# Regulators_block.net
KiCad netlist of a schematic drawn in Altium Designer
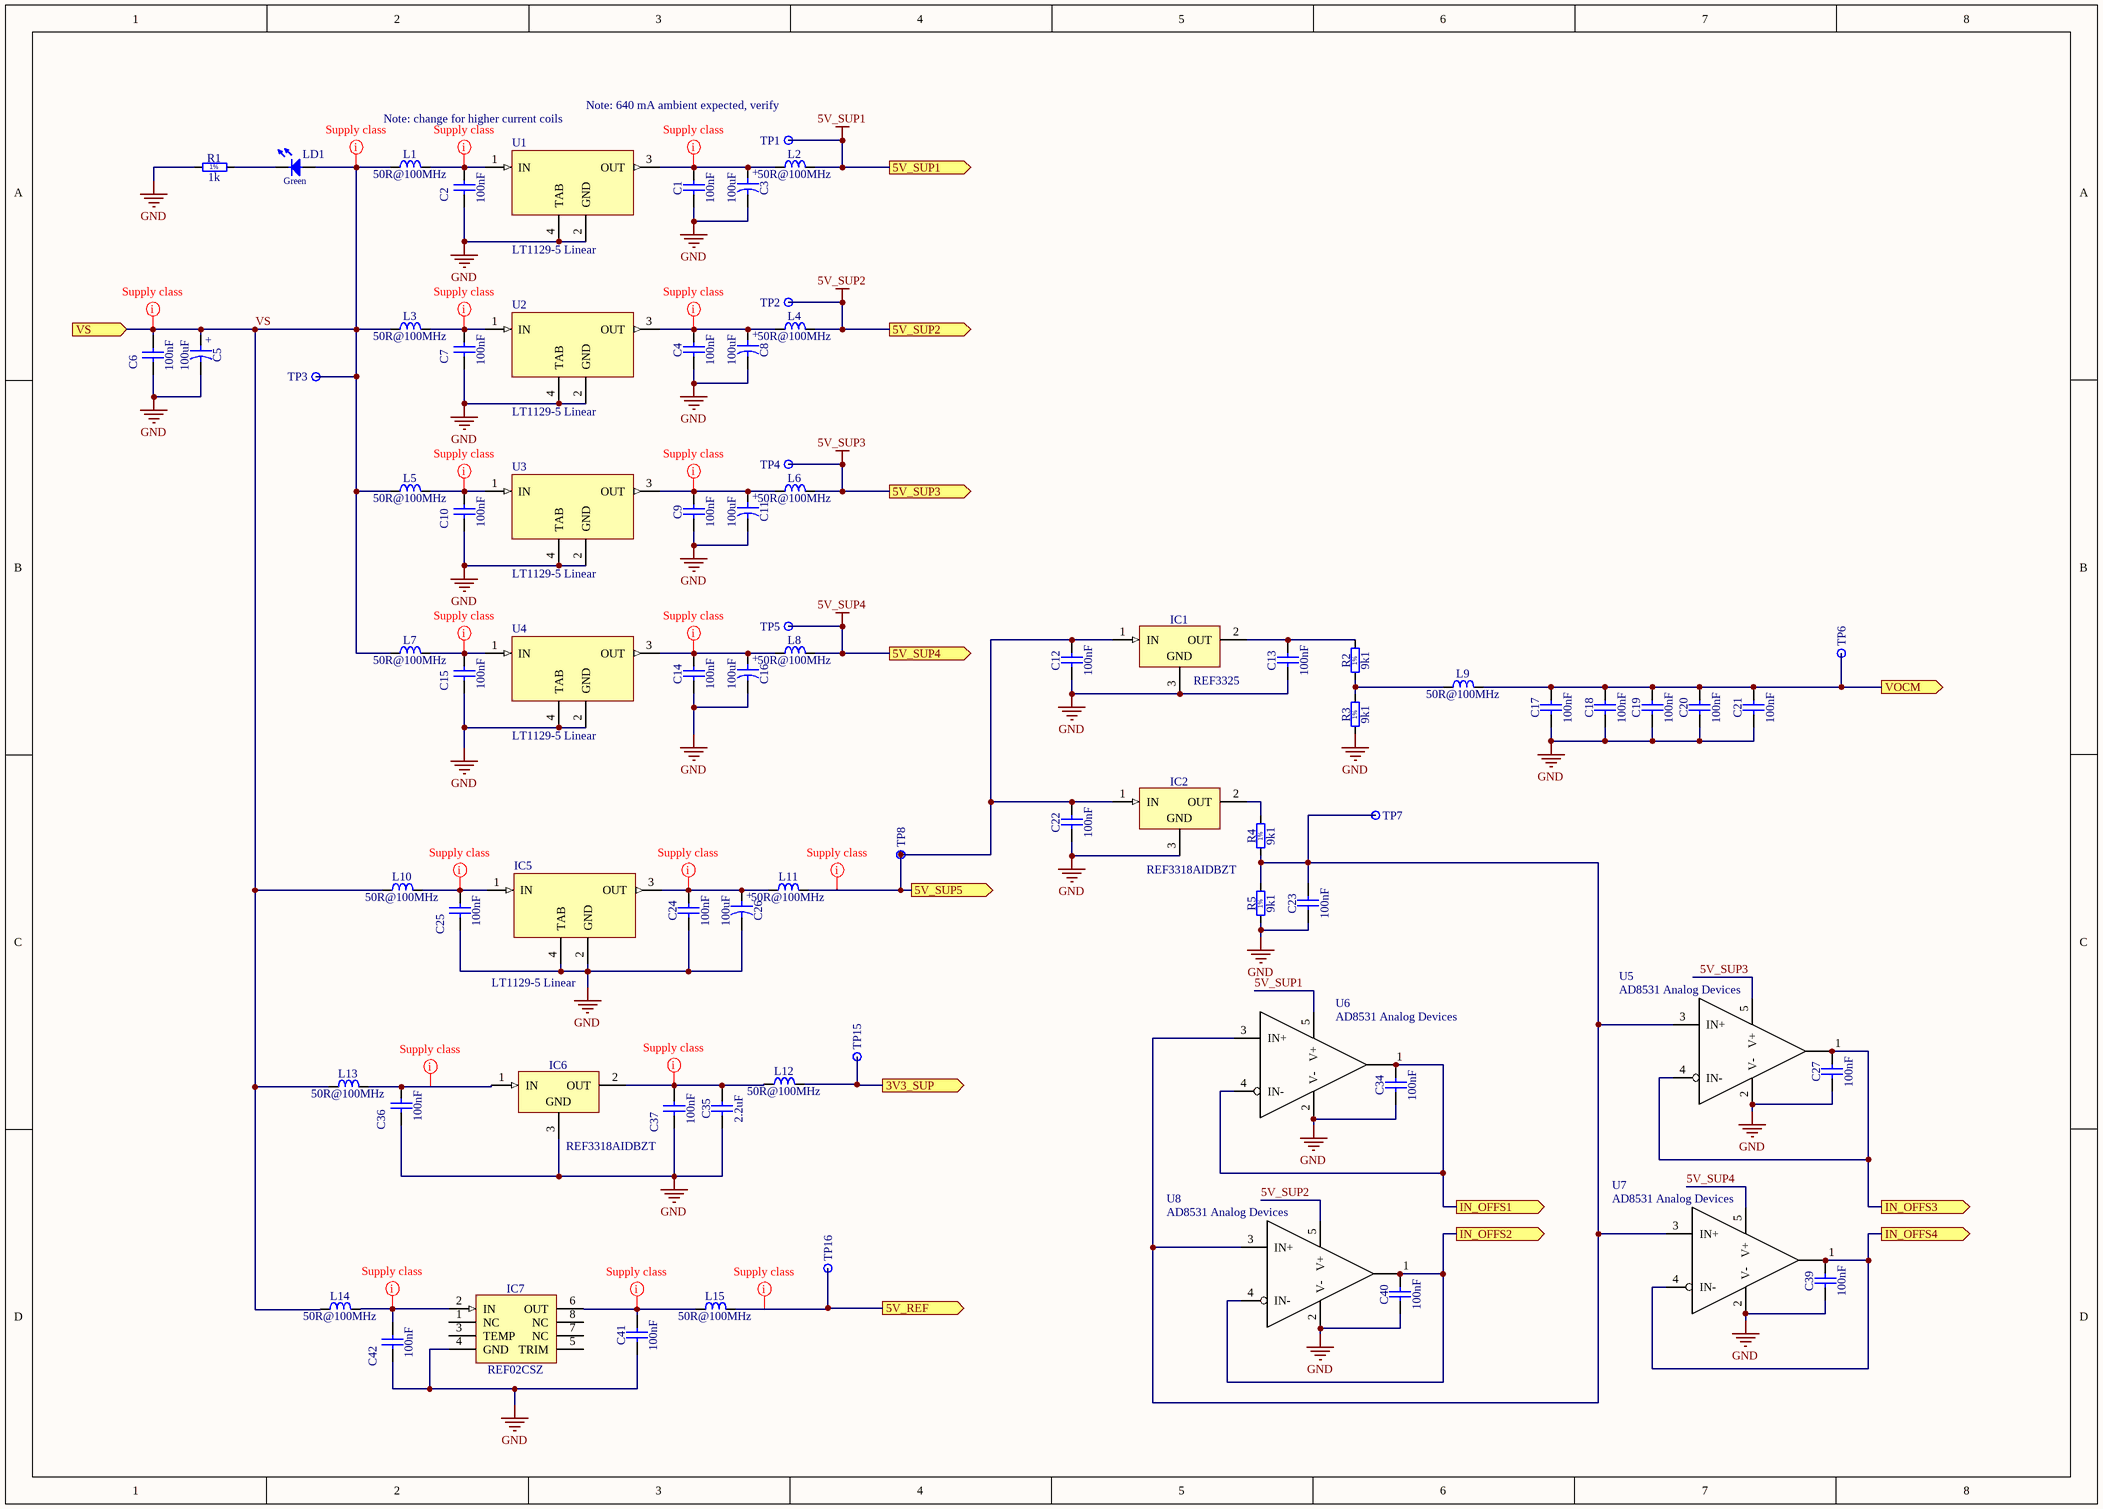
[diagram p0: Regulators_block.SchDoc]

(export (version "E")
  (design (tool "Eeschema 10.0.6"))
  (components
    (comp (ref "C1")
      (value "100nF")
      (footprint "CAPC2012X135N")
      (description "Non-polarised capacitor")
      (fields
        (field (name "PART NUMBER") "CC0805_100NF_50V_10%_X7R")
        (field (name "VOLTAGE") "50V")
        (field (name "AUTHOR") "CERN DEM JLC")
      )
      (libsource (lib "Capacitors") (part "Capacitor - non polarized"))
    )
    (comp (ref "C2")
      (value "100nF")
      (footprint "CAPC2012X135N")
      (description "Non-polarised capacitor")
      (fields
        (field (name "PART NUMBER") "CC0805_100NF_50V_10%_X7R")
        (field (name "VOLTAGE") "50V")
        (field (name "AUTHOR") "CERN DEM JLC")
      )
      (libsource (lib "Capacitors") (part "Capacitor - non polarized"))
    )
    (comp (ref "C3")
      (value "100uF")
      (footprint "CAPAE660X540N")
      (description "Polarised capacitor")
      (fields
        (field (name "PART NUMBER") "CAE660-540_100UF_16V_20%")
        (field (name "VOLTAGE") "16V")
        (field (name "AUTHOR") "CERN DEM JLC")
      )
      (libsource (lib "Capacitors") (part "Capacitor - polarized"))
    )
    (comp (ref "C4")
      (value "100nF")
      (footprint "CAPC2012X135N")
      (description "Non-polarised capacitor")
      (fields
        (field (name "PART NUMBER") "CC0805_100NF_50V_10%_X7R")
        (field (name "VOLTAGE") "50V")
        (field (name "AUTHOR") "CERN DEM JLC")
      )
      (libsource (lib "Capacitors") (part "Capacitor - non polarized"))
    )
    (comp (ref "C5")
      (value "100uF")
      (footprint "CAPAE660X540N")
      (description "Polarised capacitor")
      (fields
        (field (name "PART NUMBER") "CAE660-540_100UF_16V_20%")
        (field (name "VOLTAGE") "16V")
        (field (name "AUTHOR") "CERN DEM JLC")
      )
      (libsource (lib "Capacitors") (part "Capacitor - polarized"))
    )
    (comp (ref "C6")
      (value "100nF")
      (footprint "CAPC2012X135N")
      (description "Non-polarised capacitor")
      (fields
        (field (name "PART NUMBER") "CC0805_100NF_50V_10%_X7R")
        (field (name "VOLTAGE") "50V")
        (field (name "AUTHOR") "CERN DEM JLC")
      )
      (libsource (lib "Capacitors") (part "Capacitor - non polarized"))
    )
    (comp (ref "C7")
      (value "100nF")
      (footprint "CAPC2012X135N")
      (description "Non-polarised capacitor")
      (fields
        (field (name "PART NUMBER") "CC0805_100NF_50V_10%_X7R")
        (field (name "VOLTAGE") "50V")
        (field (name "AUTHOR") "CERN DEM JLC")
      )
      (libsource (lib "Capacitors") (part "Capacitor - non polarized"))
    )
    (comp (ref "C8")
      (value "100uF")
      (footprint "CAPAE660X540N")
      (description "Polarised capacitor")
      (fields
        (field (name "PART NUMBER") "CAE660-540_100UF_16V_20%")
        (field (name "VOLTAGE") "16V")
        (field (name "AUTHOR") "CERN DEM JLC")
      )
      (libsource (lib "Capacitors") (part "Capacitor - polarized"))
    )
    (comp (ref "C9")
      (value "100nF")
      (footprint "CAPC2012X135N")
      (description "Non-polarised capacitor")
      (fields
        (field (name "PART NUMBER") "CC0805_100NF_50V_10%_X7R")
        (field (name "VOLTAGE") "50V")
        (field (name "AUTHOR") "CERN DEM JLC")
      )
      (libsource (lib "Capacitors") (part "Capacitor - non polarized"))
    )
    (comp (ref "C10")
      (value "100nF")
      (footprint "CAPC2012X135N")
      (description "Non-polarised capacitor")
      (fields
        (field (name "PART NUMBER") "CC0805_100NF_50V_10%_X7R")
        (field (name "VOLTAGE") "50V")
        (field (name "AUTHOR") "CERN DEM JLC")
      )
      (libsource (lib "Capacitors") (part "Capacitor - non polarized"))
    )
    (comp (ref "C11")
      (value "100uF")
      (footprint "CAPAE660X540N")
      (description "Polarised capacitor")
      (fields
        (field (name "PART NUMBER") "CAE660-540_100UF_16V_20%")
        (field (name "VOLTAGE") "16V")
        (field (name "AUTHOR") "CERN DEM JLC")
      )
      (libsource (lib "Capacitors") (part "Capacitor - polarized"))
    )
    (comp (ref "C12")
      (value "100nF")
      (footprint "CAPC2012X135N")
      (description "Non-polarised capacitor")
      (fields
        (field (name "PART NUMBER") "CC0805_100NF_50V_10%_X7R")
        (field (name "VOLTAGE") "50V")
        (field (name "AUTHOR") "CERN DEM JLC")
      )
      (libsource (lib "Capacitors") (part "Capacitor - non polarized"))
    )
    (comp (ref "C13")
      (value "100nF")
      (footprint "CAPC2012X135N")
      (description "Non-polarised capacitor")
      (fields
        (field (name "PART NUMBER") "CC0805_100NF_50V_10%_X7R")
        (field (name "VOLTAGE") "50V")
        (field (name "AUTHOR") "CERN DEM JLC")
      )
      (libsource (lib "Capacitors") (part "Capacitor - non polarized"))
    )
    (comp (ref "C14")
      (value "100nF")
      (footprint "CAPC2012X135N")
      (description "Non-polarised capacitor")
      (fields
        (field (name "PART NUMBER") "CC0805_100NF_50V_10%_X7R")
        (field (name "VOLTAGE") "50V")
        (field (name "AUTHOR") "CERN DEM JLC")
      )
      (libsource (lib "Capacitors") (part "Capacitor - non polarized"))
    )
    (comp (ref "C15")
      (value "100nF")
      (footprint "CAPC2012X135N")
      (description "Non-polarised capacitor")
      (fields
        (field (name "PART NUMBER") "CC0805_100NF_50V_10%_X7R")
        (field (name "VOLTAGE") "50V")
        (field (name "AUTHOR") "CERN DEM JLC")
      )
      (libsource (lib "Capacitors") (part "Capacitor - non polarized"))
    )
    (comp (ref "C16")
      (value "100uF")
      (footprint "CAPAE660X540N")
      (description "Polarised capacitor")
      (fields
        (field (name "PART NUMBER") "CAE660-540_100UF_16V_20%")
        (field (name "VOLTAGE") "16V")
        (field (name "AUTHOR") "CERN DEM JLC")
      )
      (libsource (lib "Capacitors") (part "Capacitor - polarized"))
    )
    (comp (ref "C17")
      (value "100nF")
      (footprint "CAPC2012X135N")
      (description "Non-polarised capacitor")
      (fields
        (field (name "PART NUMBER") "CC0805_100NF_50V_10%_X7R")
        (field (name "VOLTAGE") "50V")
        (field (name "AUTHOR") "CERN DEM JLC")
      )
      (libsource (lib "Capacitors") (part "Capacitor - non polarized"))
    )
    (comp (ref "C18")
      (value "100nF")
      (footprint "CAPC2012X135N")
      (description "Non-polarised capacitor")
      (fields
        (field (name "PART NUMBER") "CC0805_100NF_50V_10%_X7R")
        (field (name "VOLTAGE") "50V")
        (field (name "AUTHOR") "CERN DEM JLC")
      )
      (libsource (lib "Capacitors") (part "Capacitor - non polarized"))
    )
    (comp (ref "C19")
      (value "100nF")
      (footprint "CAPC2012X135N")
      (description "Non-polarised capacitor")
      (fields
        (field (name "PART NUMBER") "CC0805_100NF_50V_10%_X7R")
        (field (name "VOLTAGE") "50V")
        (field (name "AUTHOR") "CERN DEM JLC")
      )
      (libsource (lib "Capacitors") (part "Capacitor - non polarized"))
    )
    (comp (ref "C20")
      (value "100nF")
      (footprint "CAPC2012X135N")
      (description "Non-polarised capacitor")
      (fields
        (field (name "PART NUMBER") "CC0805_100NF_50V_10%_X7R")
        (field (name "VOLTAGE") "50V")
        (field (name "AUTHOR") "CERN DEM JLC")
      )
      (libsource (lib "Capacitors") (part "Capacitor - non polarized"))
    )
    (comp (ref "C21")
      (value "100nF")
      (footprint "CAPC2012X135N")
      (description "Non-polarised capacitor")
      (fields
        (field (name "PART NUMBER") "CC0805_100NF_50V_10%_X7R")
        (field (name "VOLTAGE") "50V")
        (field (name "AUTHOR") "CERN DEM JLC")
      )
      (libsource (lib "Capacitors") (part "Capacitor - non polarized"))
    )
    (comp (ref "C22")
      (value "100nF")
      (footprint "CAPC2012X135N")
      (description "Non-polarised capacitor")
      (fields
        (field (name "PART NUMBER") "CC0805_100NF_50V_10%_X7R")
        (field (name "VOLTAGE") "50V")
        (field (name "AUTHOR") "CERN DEM JLC")
      )
      (libsource (lib "Capacitors") (part "Capacitor - non polarized"))
    )
    (comp (ref "C23")
      (value "100nF")
      (footprint "CAPC2012X135N")
      (description "Non-polarised capacitor")
      (fields
        (field (name "PART NUMBER") "CC0805_100NF_50V_10%_X7R")
        (field (name "VOLTAGE") "50V")
        (field (name "AUTHOR") "CERN DEM JLC")
      )
      (libsource (lib "Capacitors") (part "Capacitor - non polarized"))
    )
    (comp (ref "C24")
      (value "100nF")
      (footprint "CAPC2012X135N")
      (description "Non-polarised capacitor")
      (fields
        (field (name "PART NUMBER") "CC0805_100NF_50V_10%_X7R")
        (field (name "VOLTAGE") "50V")
        (field (name "AUTHOR") "CERN DEM JLC")
      )
      (libsource (lib "Capacitors") (part "Capacitor - non polarized"))
    )
    (comp (ref "C25")
      (value "100nF")
      (footprint "CAPC2012X135N")
      (description "Non-polarised capacitor")
      (fields
        (field (name "PART NUMBER") "CC0805_100NF_50V_10%_X7R")
        (field (name "VOLTAGE") "50V")
        (field (name "AUTHOR") "CERN DEM JLC")
      )
      (libsource (lib "Capacitors") (part "Capacitor - non polarized"))
    )
    (comp (ref "C26")
      (value "100uF")
      (footprint "CAPAE660X540N")
      (description "Polarised capacitor")
      (fields
        (field (name "PART NUMBER") "CAE660-540_100UF_16V_20%")
        (field (name "VOLTAGE") "16V")
        (field (name "AUTHOR") "CERN DEM JLC")
      )
      (libsource (lib "Capacitors") (part "Capacitor - polarized"))
    )
    (comp (ref "C27")
      (value "100nF")
      (footprint "CAPC2012X135N")
      (description "Non-polarised capacitor")
      (fields
        (field (name "PART NUMBER") "CC0805_100NF_50V_10%_X7R")
        (field (name "VOLTAGE") "50V")
        (field (name "AUTHOR") "CERN DEM JLC")
      )
      (libsource (lib "Capacitors") (part "Capacitor - non polarized"))
    )
    (comp (ref "C34")
      (value "100nF")
      (footprint "CAPC2012X135N")
      (description "Non-polarised capacitor")
      (fields
        (field (name "PART NUMBER") "CC0805_100NF_50V_10%_X7R")
        (field (name "VOLTAGE") "50V")
        (field (name "AUTHOR") "CERN DEM JLC")
      )
      (libsource (lib "Capacitors") (part "Capacitor - non polarized"))
    )
    (comp (ref "C35")
      (value "2.2uF")
      (footprint "CAPC2012X135N")
      (description "Non-polarised capacitor")
      (fields
        (field (name "PART NUMBER") "CC0805_2.2UF_16V_10%_X7R")
        (field (name "VOLTAGE") "16V")
        (field (name "AUTHOR") "CERN DEM JLC")
      )
      (libsource (lib "Capacitors") (part "Capacitor - non polarized"))
    )
    (comp (ref "C36")
      (value "100nF")
      (footprint "CAPC2012X135N")
      (description "Non-polarised capacitor")
      (fields
        (field (name "PART NUMBER") "CC0805_100NF_50V_10%_X7R")
        (field (name "VOLTAGE") "50V")
        (field (name "AUTHOR") "CERN DEM JLC")
      )
      (libsource (lib "Capacitors") (part "Capacitor - non polarized"))
    )
    (comp (ref "C37")
      (value "100nF")
      (footprint "CAPC2012X135N")
      (description "Non-polarised capacitor")
      (fields
        (field (name "PART NUMBER") "CC0805_100NF_50V_10%_X7R")
        (field (name "VOLTAGE") "50V")
        (field (name "AUTHOR") "CERN DEM JLC")
      )
      (libsource (lib "Capacitors") (part "Capacitor - non polarized"))
    )
    (comp (ref "C39")
      (value "100nF")
      (footprint "CAPC2012X135N")
      (description "Non-polarised capacitor")
      (fields
        (field (name "PART NUMBER") "CC0805_100NF_50V_10%_X7R")
        (field (name "VOLTAGE") "50V")
        (field (name "AUTHOR") "CERN DEM JLC")
      )
      (libsource (lib "Capacitors") (part "Capacitor - non polarized"))
    )
    (comp (ref "C40")
      (value "100nF")
      (footprint "CAPC2012X135N")
      (description "Non-polarised capacitor")
      (fields
        (field (name "PART NUMBER") "CC0805_100NF_50V_10%_X7R")
        (field (name "VOLTAGE") "50V")
        (field (name "AUTHOR") "CERN DEM JLC")
      )
      (libsource (lib "Capacitors") (part "Capacitor - non polarized"))
    )
    (comp (ref "C41")
      (value "100nF")
      (footprint "CAPC2012X135N")
      (description "Non-polarised capacitor")
      (fields
        (field (name "PART NUMBER") "CC0805_100NF_50V_10%_X7R")
        (field (name "VOLTAGE") "50V")
        (field (name "AUTHOR") "CERN DEM JLC")
      )
      (libsource (lib "Capacitors") (part "Capacitor - non polarized"))
    )
    (comp (ref "C42")
      (value "100nF")
      (footprint "CAPC2012X135N")
      (description "Non-polarised capacitor")
      (fields
        (field (name "PART NUMBER") "CC0805_100NF_50V_10%_X7R")
        (field (name "VOLTAGE") "50V")
        (field (name "AUTHOR") "CERN DEM JLC")
      )
      (libsource (lib "Capacitors") (part "Capacitor - non polarized"))
    )
    (comp (ref "IC1")
      (value "REF3325")
      (footprint "SOT95P237X112-3N")
      (description "3-Terminal Regulator 1=IN 2=OUT 3=GND")
      (fields (field (name "MANUFACTURER") "TEXAS INSTRUMENTS") (field (name "AUTHOR") "CERN DEM JLC"))
      (libsource (lib "ICs And Semiconductors") (part "REG3 1IN-2OUT-3GND"))
    )
    (comp (ref "IC2")
      (value "REF3318AIDBZT")
      (footprint "SOT95P237X112-3N")
      (description "3-Terminal Regulator 1=IN 2=OUT 3=GND")
      (fields (field (name "MANUFACTURER") "TEXAS INSTRUMENTS") (field (name "AUTHOR") "CERN DEM JLC"))
      (libsource (lib "ICs And Semiconductors") (part "REG3 1IN-2OUT-3GND"))
    )
    (comp (ref "IC5")
      (value "LT1129-5 Linear")
      (footprint "SOT230P700X175-4N")
      (fields (field (name "MANUFACTURER") "Linear"))
      (libsource (lib "Additional") (part "LT1129-5"))
    )
    (comp (ref "IC6")
      (value "REF3318AIDBZT")
      (footprint "SOT95P237X112-3N")
      (description "3-Terminal Regulator 1=IN 2=OUT 3=GND")
      (fields (field (name "MANUFACTURER") "TEXAS INSTRUMENTS") (field (name "AUTHOR") "CERN DEM JLC"))
      (libsource (lib "ICs And Semiconductors") (part "REG3 1IN-2OUT-3GND"))
    )
    (comp (ref "IC7")
      (value "REF02CSZ")
      (footprint "SOIC127P600X175-8N")
      (description "Precision Voltage Reference/Temperature Transducer")
      (fields (field (name "MANUFACTURER") "ANALOG DEVICES") (field (name "AUTHOR") "CERN DEM JLC"))
      (libsource (lib "ICs And Semiconductors") (part "REF02CSZ"))
    )
    (comp (ref "L1")
      (value "50R@100MHz")
      (footprint "IND_MURATA_BLM31PG")
      (description "Inductor")
      (fields
        (field (name "PART NUMBER") "IND1206_MURATA_BLM31PG500SN1")
        (field (name "POWER") "3.5A")
        (field (name "AUTHOR") "CERN DEM JLC")
      )
      (libsource (lib "Inductors & Transformers") (part "Inductor"))
    )
    (comp (ref "L2")
      (value "50R@100MHz")
      (footprint "IND_MURATA_BLM31PG")
      (description "Inductor")
      (fields
        (field (name "PART NUMBER") "IND1206_MURATA_BLM31PG500SN1")
        (field (name "POWER") "3.5A")
        (field (name "AUTHOR") "CERN DEM JLC")
      )
      (libsource (lib "Inductors & Transformers") (part "Inductor"))
    )
    (comp (ref "L3")
      (value "50R@100MHz")
      (footprint "IND_MURATA_BLM31PG")
      (description "Inductor")
      (fields
        (field (name "PART NUMBER") "IND1206_MURATA_BLM31PG500SN1")
        (field (name "POWER") "3.5A")
        (field (name "AUTHOR") "CERN DEM JLC")
      )
      (libsource (lib "Inductors & Transformers") (part "Inductor"))
    )
    (comp (ref "L4")
      (value "50R@100MHz")
      (footprint "IND_MURATA_BLM31PG")
      (description "Inductor")
      (fields
        (field (name "PART NUMBER") "IND1206_MURATA_BLM31PG500SN1")
        (field (name "POWER") "3.5A")
        (field (name "AUTHOR") "CERN DEM JLC")
      )
      (libsource (lib "Inductors & Transformers") (part "Inductor"))
    )
    (comp (ref "L5")
      (value "50R@100MHz")
      (footprint "IND_MURATA_BLM31PG")
      (description "Inductor")
      (fields
        (field (name "PART NUMBER") "IND1206_MURATA_BLM31PG500SN1")
        (field (name "POWER") "3.5A")
        (field (name "AUTHOR") "CERN DEM JLC")
      )
      (libsource (lib "Inductors & Transformers") (part "Inductor"))
    )
    (comp (ref "L6")
      (value "50R@100MHz")
      (footprint "IND_MURATA_BLM31PG")
      (description "Inductor")
      (fields
        (field (name "PART NUMBER") "IND1206_MURATA_BLM31PG500SN1")
        (field (name "POWER") "3.5A")
        (field (name "AUTHOR") "CERN DEM JLC")
      )
      (libsource (lib "Inductors & Transformers") (part "Inductor"))
    )
    (comp (ref "L7")
      (value "50R@100MHz")
      (footprint "IND_MURATA_BLM31PG")
      (description "Inductor")
      (fields
        (field (name "PART NUMBER") "IND1206_MURATA_BLM31PG500SN1")
        (field (name "POWER") "3.5A")
        (field (name "AUTHOR") "CERN DEM JLC")
      )
      (libsource (lib "Inductors & Transformers") (part "Inductor"))
    )
    (comp (ref "L8")
      (value "50R@100MHz")
      (footprint "IND_MURATA_BLM31PG")
      (description "Inductor")
      (fields
        (field (name "PART NUMBER") "IND1206_MURATA_BLM31PG500SN1")
        (field (name "POWER") "3.5A")
        (field (name "AUTHOR") "CERN DEM JLC")
      )
      (libsource (lib "Inductors & Transformers") (part "Inductor"))
    )
    (comp (ref "L9")
      (value "50R@100MHz")
      (footprint "IND_MURATA_BLM31PG")
      (description "Inductor")
      (fields
        (field (name "PART NUMBER") "IND1206_MURATA_BLM31PG500SN1")
        (field (name "POWER") "3.5A")
        (field (name "AUTHOR") "CERN DEM JLC")
      )
      (libsource (lib "Inductors & Transformers") (part "Inductor"))
    )
    (comp (ref "L10")
      (value "50R@100MHz")
      (footprint "IND_MURATA_BLM31PG")
      (description "Inductor")
      (fields
        (field (name "PART NUMBER") "IND1206_MURATA_BLM31PG500SN1")
        (field (name "POWER") "3.5A")
        (field (name "AUTHOR") "CERN DEM JLC")
      )
      (libsource (lib "Inductors & Transformers") (part "Inductor"))
    )
    (comp (ref "L11")
      (value "50R@100MHz")
      (footprint "IND_MURATA_BLM31PG")
      (description "Inductor")
      (fields
        (field (name "PART NUMBER") "IND1206_MURATA_BLM31PG500SN1")
        (field (name "POWER") "3.5A")
        (field (name "AUTHOR") "CERN DEM JLC")
      )
      (libsource (lib "Inductors & Transformers") (part "Inductor"))
    )
    (comp (ref "L12")
      (value "50R@100MHz")
      (footprint "IND_MURATA_BLM31PG")
      (description "Inductor")
      (fields
        (field (name "PART NUMBER") "IND1206_MURATA_BLM31PG500SN1")
        (field (name "POWER") "3.5A")
        (field (name "AUTHOR") "CERN DEM JLC")
      )
      (libsource (lib "Inductors & Transformers") (part "Inductor"))
    )
    (comp (ref "L13")
      (value "50R@100MHz")
      (footprint "IND_MURATA_BLM31PG")
      (description "Inductor")
      (fields
        (field (name "PART NUMBER") "IND1206_MURATA_BLM31PG500SN1")
        (field (name "POWER") "3.5A")
        (field (name "AUTHOR") "CERN DEM JLC")
      )
      (libsource (lib "Inductors & Transformers") (part "Inductor"))
    )
    (comp (ref "L14")
      (value "50R@100MHz")
      (footprint "IND_MURATA_BLM31PG")
      (description "Inductor")
      (fields
        (field (name "PART NUMBER") "IND1206_MURATA_BLM31PG500SN1")
        (field (name "POWER") "3.5A")
        (field (name "AUTHOR") "CERN DEM JLC")
      )
      (libsource (lib "Inductors & Transformers") (part "Inductor"))
    )
    (comp (ref "L15")
      (value "50R@100MHz")
      (footprint "IND_MURATA_BLM31PG")
      (description "Inductor")
      (fields
        (field (name "PART NUMBER") "IND1206_MURATA_BLM31PG500SN1")
        (field (name "POWER") "3.5A")
        (field (name "AUTHOR") "CERN DEM JLC")
      )
      (libsource (lib "Inductors & Transformers") (part "Inductor"))
    )
    (comp (ref "LD1")
      (value "Green")
      (footprint "LED_OSRAM_LGR971")
      (description "LED Green 1C 2A")
      (fields
        (field (name "PART NUMBER") "LED_OSRAM_LGR971")
        (field (name "MANUFACTURER") "OSRAM")
        (field (name "AUTHOR") "CERN DEM JLC")
      )
      (libsource (lib "ICs And Semiconductors") (part "LED Green 1C 2A"))
    )
    (comp (ref "R1")
      (value "1k")
      (footprint "RESC2012X60N")
      (description "Resistor - 1%")
      (fields
        (field (name "PART NUMBER") "R0805_1K_1%_0.125W_100PPM")
        (field (name "POWER") "0.125W")
        (field (name "AUTHOR") "CERN DEM JLC")
      )
      (libsource (lib "Resistors") (part "Resistor - 1%"))
    )
    (comp (ref "R2")
      (value "9k1")
      (footprint "RESC2012X60N")
      (description "Resistor - 1%")
      (fields
        (field (name "PART NUMBER") "R0805_9K1_1%_0.125W_100PPM")
        (field (name "POWER") "0.125W")
        (field (name "AUTHOR") "CERN DEM JLC")
      )
      (libsource (lib "Resistors") (part "Resistor - 1%"))
    )
    (comp (ref "R3")
      (value "9k1")
      (footprint "RESC2012X60N")
      (description "Resistor - 1%")
      (fields
        (field (name "PART NUMBER") "R0805_9K1_1%_0.125W_100PPM")
        (field (name "POWER") "0.125W")
        (field (name "AUTHOR") "CERN DEM JLC")
      )
      (libsource (lib "Resistors") (part "Resistor - 1%"))
    )
    (comp (ref "R4")
      (value "9k1")
      (footprint "RESC2012X60N")
      (description "Resistor - 1%")
      (fields
        (field (name "PART NUMBER") "R0805_9K1_1%_0.125W_100PPM")
        (field (name "POWER") "0.125W")
        (field (name "AUTHOR") "CERN DEM JLC")
      )
      (libsource (lib "Resistors") (part "Resistor - 1%"))
    )
    (comp (ref "R5")
      (value "9k1")
      (footprint "RESC2012X60N")
      (description "Resistor - 1%")
      (fields
        (field (name "PART NUMBER") "R0805_9K1_1%_0.125W_100PPM")
        (field (name "POWER") "0.125W")
        (field (name "AUTHOR") "CERN DEM JLC")
      )
      (libsource (lib "Resistors") (part "Resistor - 1%"))
    )
    (comp (ref "TP1")
      (value "Test Point")
      (footprint "VERO_20-313145")
      (fields
        (field (name "PART NUMBER") "VERO_20-313145")
        (field (name "MANUFACTURER") "VERO TECHNOLOGIES")
        (field (name "MANUFACTURER PART NUMBER") "20-313145")
        (field (name "AUTHOR") "CERN DEM JLC")
      )
      (libsource (lib "Connectors") (part "Test Point"))
    )
    (comp (ref "TP2")
      (value "Test Point")
      (footprint "VERO_20-313145")
      (fields
        (field (name "PART NUMBER") "VERO_20-313145")
        (field (name "MANUFACTURER") "VERO TECHNOLOGIES")
        (field (name "MANUFACTURER PART NUMBER") "20-313145")
        (field (name "AUTHOR") "CERN DEM JLC")
      )
      (libsource (lib "Connectors") (part "Test Point"))
    )
    (comp (ref "TP3")
      (value "Test Point")
      (footprint "VERO_20-313145")
      (fields
        (field (name "PART NUMBER") "VERO_20-313145")
        (field (name "MANUFACTURER") "VERO TECHNOLOGIES")
        (field (name "MANUFACTURER PART NUMBER") "20-313145")
        (field (name "AUTHOR") "CERN DEM JLC")
      )
      (libsource (lib "Connectors") (part "Test Point"))
    )
    (comp (ref "TP4")
      (value "Test Point")
      (footprint "VERO_20-313145")
      (fields
        (field (name "PART NUMBER") "VERO_20-313145")
        (field (name "MANUFACTURER") "VERO TECHNOLOGIES")
        (field (name "MANUFACTURER PART NUMBER") "20-313145")
        (field (name "AUTHOR") "CERN DEM JLC")
      )
      (libsource (lib "Connectors") (part "Test Point"))
    )
    (comp (ref "TP5")
      (value "Test Point")
      (footprint "VERO_20-313145")
      (fields
        (field (name "PART NUMBER") "VERO_20-313145")
        (field (name "MANUFACTURER") "VERO TECHNOLOGIES")
        (field (name "MANUFACTURER PART NUMBER") "20-313145")
        (field (name "AUTHOR") "CERN DEM JLC")
      )
      (libsource (lib "Connectors") (part "Test Point"))
    )
    (comp (ref "TP6")
      (value "Test Point")
      (footprint "VERO_20-313145")
      (fields
        (field (name "PART NUMBER") "VERO_20-313145")
        (field (name "MANUFACTURER") "VERO TECHNOLOGIES")
        (field (name "MANUFACTURER PART NUMBER") "20-313145")
        (field (name "AUTHOR") "CERN DEM JLC")
      )
      (libsource (lib "Connectors") (part "Test Point"))
    )
    (comp (ref "TP7")
      (value "Test Point")
      (footprint "VERO_20-313145")
      (fields
        (field (name "PART NUMBER") "VERO_20-313145")
        (field (name "MANUFACTURER") "VERO TECHNOLOGIES")
        (field (name "MANUFACTURER PART NUMBER") "20-313145")
        (field (name "AUTHOR") "CERN DEM JLC")
      )
      (libsource (lib "Connectors") (part "Test Point"))
    )
    (comp (ref "TP8")
      (value "Test Point")
      (footprint "VERO_20-2136")
      (fields
        (field (name "PART NUMBER") "VERO_20-2136")
        (field (name "MANUFACTURER") "VERO TECHNOLOGIES")
        (field (name "MANUFACTURER PART NUMBER") "20-2136")
        (field (name "AUTHOR") "CERN DEM JLC")
      )
      (libsource (lib "Connectors") (part "Test Point"))
    )
    (comp (ref "TP15")
      (value "Test Point")
      (footprint "VERO_20-2136")
      (fields
        (field (name "PART NUMBER") "VERO_20-2136")
        (field (name "MANUFACTURER") "VERO TECHNOLOGIES")
        (field (name "MANUFACTURER PART NUMBER") "20-2136")
        (field (name "AUTHOR") "CERN DEM JLC")
      )
      (libsource (lib "Connectors") (part "Test Point"))
    )
    (comp (ref "TP16")
      (value "Test Point")
      (footprint "VERO_20-2136")
      (fields
        (field (name "PART NUMBER") "VERO_20-2136")
        (field (name "MANUFACTURER") "VERO TECHNOLOGIES")
        (field (name "MANUFACTURER PART NUMBER") "20-2136")
        (field (name "AUTHOR") "CERN DEM JLC")
      )
      (libsource (lib "Connectors") (part "Test Point"))
    )
    (comp (ref "U1")
      (value "LT1129-5 Linear")
      (footprint "SOT230P700X175-4N")
      (fields (field (name "MANUFACTURER") "Linear"))
      (libsource (lib "Additional") (part "LT1129-5"))
    )
    (comp (ref "U2")
      (value "LT1129-5 Linear")
      (footprint "SOT230P700X175-4N")
      (fields (field (name "MANUFACTURER") "Linear"))
      (libsource (lib "Additional") (part "LT1129-5"))
    )
    (comp (ref "U3")
      (value "LT1129-5 Linear")
      (footprint "SOT230P700X175-4N")
      (fields (field (name "MANUFACTURER") "Linear"))
      (libsource (lib "Additional") (part "LT1129-5"))
    )
    (comp (ref "U4")
      (value "LT1129-5 Linear")
      (footprint "SOT230P700X175-4N")
      (fields (field (name "MANUFACTURER") "Linear"))
      (libsource (lib "Additional") (part "LT1129-5"))
    )
    (comp (ref "U5")
      (value "AD8531 Analog Devices")
      (footprint "SOT95P285X145-5N")
      (fields (field (name "MANUFACTURER") "Analog Devices"))
      (libsource (lib "Additional") (part "AD8531"))
    )
    (comp (ref "U6")
      (value "AD8531 Analog Devices")
      (footprint "SOT95P285X145-5N")
      (fields (field (name "MANUFACTURER") "Analog Devices"))
      (libsource (lib "Additional") (part "AD8531"))
    )
    (comp (ref "U7")
      (value "AD8531 Analog Devices")
      (footprint "SOT95P285X145-5N")
      (fields (field (name "MANUFACTURER") "Analog Devices"))
      (libsource (lib "Additional") (part "AD8531"))
    )
    (comp (ref "U8")
      (value "AD8531 Analog Devices")
      (footprint "SOT95P285X145-5N")
      (fields (field (name "MANUFACTURER") "Analog Devices"))
      (libsource (lib "Additional") (part "AD8531"))
    )
  )
  (nets
    (net (code "1") (name "/3V3_SUP") (class "Default")
      (node (ref "L12") (pin "2") (pinfunction "2_2") (pintype "passive"))
      (node (ref "TP15") (pin "1") (pinfunction "1_1") (pintype "bidirectional"))
    )
    (net (code "2") (name "/5V_REF") (class "Default")
      (node (ref "L15") (pin "2") (pinfunction "2_2") (pintype "passive"))
      (node (ref "TP16") (pin "1") (pinfunction "1_1") (pintype "bidirectional"))
    )
    (net (code "3") (name "/5V_SUP5") (class "Default")
      (node (ref "C12") (pin "2") (pinfunction "2_2") (pintype "passive"))
      (node (ref "C22") (pin "2") (pinfunction "2_2") (pintype "passive"))
      (node (ref "IC1") (pin "1") (pinfunction "IN_1") (pintype "input"))
      (node (ref "IC2") (pin "1") (pinfunction "IN_1") (pintype "input"))
      (node (ref "L11") (pin "2") (pinfunction "2_2") (pintype "passive"))
      (node (ref "TP8") (pin "1") (pinfunction "1_1") (pintype "bidirectional"))
    )
    (net (code "4") (name "/IN_OFFS1") (class "Default")
      (node (ref "C34") (pin "2") (pinfunction "2_2") (pintype "passive"))
      (node (ref "U6") (pin "1") (pinfunction "OUT+_1") (pintype "passive"))
      (node (ref "U6") (pin "4") (pinfunction "IN-_4") (pintype "passive"))
    )
    (net (code "5") (name "/IN_OFFS2") (class "Default")
      (node (ref "C40") (pin "2") (pinfunction "2_2") (pintype "passive"))
      (node (ref "U8") (pin "1") (pinfunction "OUT+_1") (pintype "passive"))
      (node (ref "U8") (pin "4") (pinfunction "IN-_4") (pintype "passive"))
    )
    (net (code "6") (name "/IN_OFFS3") (class "Default")
      (node (ref "C27") (pin "2") (pinfunction "2_2") (pintype "passive"))
      (node (ref "U5") (pin "1") (pinfunction "OUT+_1") (pintype "passive"))
      (node (ref "U5") (pin "4") (pinfunction "IN-_4") (pintype "passive"))
    )
    (net (code "7") (name "/IN_OFFS4") (class "Default")
      (node (ref "C39") (pin "2") (pinfunction "2_2") (pintype "passive"))
      (node (ref "U7") (pin "1") (pinfunction "OUT+_1") (pintype "passive"))
      (node (ref "U7") (pin "4") (pinfunction "IN-_4") (pintype "passive"))
    )
    (net (code "8") (name "/VOCM") (class "Default")
      (node (ref "C17") (pin "2") (pinfunction "2_2") (pintype "passive"))
      (node (ref "C18") (pin "2") (pinfunction "2_2") (pintype "passive"))
      (node (ref "C19") (pin "2") (pinfunction "2_2") (pintype "passive"))
      (node (ref "C20") (pin "2") (pinfunction "2_2") (pintype "passive"))
      (node (ref "C21") (pin "2") (pinfunction "2_2") (pintype "passive"))
      (node (ref "L9") (pin "2") (pinfunction "2_2") (pintype "passive"))
      (node (ref "TP6") (pin "1") (pinfunction "1_1") (pintype "bidirectional"))
    )
    (net (code "9") (name "/VS") (class "Default")
      (node (ref "C5") (pin "1") (pinfunction "1_1") (pintype "passive"))
      (node (ref "C6") (pin "2") (pinfunction "2_2") (pintype "passive"))
      (node (ref "L1") (pin "1") (pinfunction "1_1") (pintype "passive"))
      (node (ref "L10") (pin "1") (pinfunction "1_1") (pintype "passive"))
      (node (ref "L13") (pin "1") (pinfunction "1_1") (pintype "passive"))
      (node (ref "L14") (pin "1") (pinfunction "1_1") (pintype "passive"))
      (node (ref "L3") (pin "1") (pinfunction "1_1") (pintype "passive"))
      (node (ref "L5") (pin "1") (pinfunction "1_1") (pintype "passive"))
      (node (ref "L7") (pin "1") (pinfunction "1_1") (pintype "passive"))
      (node (ref "LD1") (pin "2") (pinfunction "A_2") (pintype "passive"))
      (node (ref "TP3") (pin "1") (pinfunction "1_1") (pintype "bidirectional"))
    )
    (net (code "10") (name "5V_SUP1") (class "Default")
      (node (ref "L2") (pin "2") (pinfunction "2_2") (pintype "passive"))
      (node (ref "TP1") (pin "1") (pinfunction "1_1") (pintype "bidirectional"))
      (node (ref "U6") (pin "5") (pinfunction "V+_5") (pintype "passive"))
    )
    (net (code "11") (name "5V_SUP2") (class "Default")
      (node (ref "L4") (pin "2") (pinfunction "2_2") (pintype "passive"))
      (node (ref "TP2") (pin "1") (pinfunction "1_1") (pintype "bidirectional"))
      (node (ref "U8") (pin "5") (pinfunction "V+_5") (pintype "passive"))
    )
    (net (code "12") (name "5V_SUP3") (class "Default")
      (node (ref "L6") (pin "2") (pinfunction "2_2") (pintype "passive"))
      (node (ref "TP4") (pin "1") (pinfunction "1_1") (pintype "bidirectional"))
      (node (ref "U5") (pin "5") (pinfunction "V+_5") (pintype "passive"))
    )
    (net (code "13") (name "5V_SUP4") (class "Default")
      (node (ref "L8") (pin "2") (pinfunction "2_2") (pintype "passive"))
      (node (ref "TP5") (pin "1") (pinfunction "1_1") (pintype "bidirectional"))
      (node (ref "U7") (pin "5") (pinfunction "V+_5") (pintype "passive"))
    )
    (net (code "14") (name "GND") (class "Default")
      (node (ref "C1") (pin "1") (pinfunction "1_1") (pintype "passive"))
      (node (ref "C10") (pin "1") (pinfunction "1_1") (pintype "passive"))
      (node (ref "C11") (pin "2") (pinfunction "2_2") (pintype "passive"))
      (node (ref "C12") (pin "1") (pinfunction "1_1") (pintype "passive"))
      (node (ref "C13") (pin "1") (pinfunction "1_1") (pintype "passive"))
      (node (ref "C14") (pin "1") (pinfunction "1_1") (pintype "passive"))
      (node (ref "C15") (pin "1") (pinfunction "1_1") (pintype "passive"))
      (node (ref "C16") (pin "2") (pinfunction "2_2") (pintype "passive"))
      (node (ref "C17") (pin "1") (pinfunction "1_1") (pintype "passive"))
      (node (ref "C18") (pin "1") (pinfunction "1_1") (pintype "passive"))
      (node (ref "C19") (pin "1") (pinfunction "1_1") (pintype "passive"))
      (node (ref "C2") (pin "1") (pinfunction "1_1") (pintype "passive"))
      (node (ref "C20") (pin "1") (pinfunction "1_1") (pintype "passive"))
      (node (ref "C21") (pin "1") (pinfunction "1_1") (pintype "passive"))
      (node (ref "C22") (pin "1") (pinfunction "1_1") (pintype "passive"))
      (node (ref "C23") (pin "1") (pinfunction "1_1") (pintype "passive"))
      (node (ref "C24") (pin "1") (pinfunction "1_1") (pintype "passive"))
      (node (ref "C25") (pin "1") (pinfunction "1_1") (pintype "passive"))
      (node (ref "C26") (pin "2") (pinfunction "2_2") (pintype "passive"))
      (node (ref "C27") (pin "1") (pinfunction "1_1") (pintype "passive"))
      (node (ref "C3") (pin "2") (pinfunction "2_2") (pintype "passive"))
      (node (ref "C34") (pin "1") (pinfunction "1_1") (pintype "passive"))
      (node (ref "C35") (pin "1") (pinfunction "1_1") (pintype "passive"))
      (node (ref "C36") (pin "1") (pinfunction "1_1") (pintype "passive"))
      (node (ref "C37") (pin "1") (pinfunction "1_1") (pintype "passive"))
      (node (ref "C39") (pin "1") (pinfunction "1_1") (pintype "passive"))
      (node (ref "C4") (pin "1") (pinfunction "1_1") (pintype "passive"))
      (node (ref "C40") (pin "1") (pinfunction "1_1") (pintype "passive"))
      (node (ref "C41") (pin "1") (pinfunction "1_1") (pintype "passive"))
      (node (ref "C42") (pin "1") (pinfunction "1_1") (pintype "passive"))
      (node (ref "C5") (pin "2") (pinfunction "2_2") (pintype "passive"))
      (node (ref "C6") (pin "1") (pinfunction "1_1") (pintype "passive"))
      (node (ref "C7") (pin "1") (pinfunction "1_1") (pintype "passive"))
      (node (ref "C8") (pin "2") (pinfunction "2_2") (pintype "passive"))
      (node (ref "C9") (pin "1") (pinfunction "1_1") (pintype "passive"))
      (node (ref "IC1") (pin "3") (pinfunction "GND_3") (pintype "power_in"))
      (node (ref "IC2") (pin "3") (pinfunction "GND_3") (pintype "power_in"))
      (node (ref "IC5") (pin "2") (pinfunction "GND_2") (pintype "power_in"))
      (node (ref "IC5") (pin "4") (pinfunction "TAB_4") (pintype "power_in"))
      (node (ref "IC6") (pin "3") (pinfunction "GND_3") (pintype "power_in"))
      (node (ref "IC7") (pin "4") (pinfunction "GND_4") (pintype "power_in"))
      (node (ref "R1") (pin "1") (pinfunction "1_1") (pintype "passive"))
      (node (ref "R3") (pin "1") (pinfunction "1_1") (pintype "passive"))
      (node (ref "R5") (pin "1") (pinfunction "1_1") (pintype "passive"))
      (node (ref "U1") (pin "2") (pinfunction "GND_2") (pintype "power_in"))
      (node (ref "U1") (pin "4") (pinfunction "TAB_4") (pintype "power_in"))
      (node (ref "U2") (pin "2") (pinfunction "GND_2") (pintype "power_in"))
      (node (ref "U2") (pin "4") (pinfunction "TAB_4") (pintype "power_in"))
      (node (ref "U3") (pin "2") (pinfunction "GND_2") (pintype "power_in"))
      (node (ref "U3") (pin "4") (pinfunction "TAB_4") (pintype "power_in"))
      (node (ref "U4") (pin "2") (pinfunction "GND_2") (pintype "power_in"))
      (node (ref "U4") (pin "4") (pinfunction "TAB_4") (pintype "power_in"))
      (node (ref "U5") (pin "2") (pinfunction "V-_2") (pintype "passive"))
      (node (ref "U6") (pin "2") (pinfunction "V-_2") (pintype "passive"))
      (node (ref "U7") (pin "2") (pinfunction "V-_2") (pintype "passive"))
      (node (ref "U8") (pin "2") (pinfunction "V-_2") (pintype "passive"))
    )
    (net (code "15") (name "Net-(IC1-OUT)") (class "Default")
      (node (ref "C13") (pin "2") (pinfunction "2_2") (pintype "passive"))
      (node (ref "IC1") (pin "2") (pinfunction "OUT_2") (pintype "power_in"))
      (node (ref "R2") (pin "2") (pinfunction "2_2") (pintype "passive"))
    )
    (net (code "16") (name "Net-(IC2-OUT)") (class "Default")
      (node (ref "IC2") (pin "2") (pinfunction "OUT_2") (pintype "power_in"))
      (node (ref "R4") (pin "2") (pinfunction "2_2") (pintype "passive"))
    )
    (net (code "17") (name "Net-(IC5-IN)") (class "Default")
      (node (ref "C25") (pin "2") (pinfunction "2_2") (pintype "passive"))
      (node (ref "IC5") (pin "1") (pinfunction "IN_1") (pintype "input"))
      (node (ref "L10") (pin "2") (pinfunction "2_2") (pintype "passive"))
    )
    (net (code "18") (name "Net-(IC5-OUT)") (class "Default")
      (node (ref "C24") (pin "2") (pinfunction "2_2") (pintype "passive"))
      (node (ref "C26") (pin "1") (pinfunction "1_1") (pintype "passive"))
      (node (ref "IC5") (pin "3") (pinfunction "OUT_3") (pintype "output"))
      (node (ref "L11") (pin "1") (pinfunction "1_1") (pintype "passive"))
    )
    (net (code "19") (name "Net-(IC6-IN)") (class "Default")
      (node (ref "C36") (pin "2") (pinfunction "2_2") (pintype "passive"))
      (node (ref "IC6") (pin "1") (pinfunction "IN_1") (pintype "input"))
      (node (ref "L13") (pin "2") (pinfunction "2_2") (pintype "passive"))
    )
    (net (code "20") (name "Net-(IC6-OUT)") (class "Default")
      (node (ref "C35") (pin "2") (pinfunction "2_2") (pintype "passive"))
      (node (ref "C37") (pin "2") (pinfunction "2_2") (pintype "passive"))
      (node (ref "IC6") (pin "2") (pinfunction "OUT_2") (pintype "power_in"))
      (node (ref "L12") (pin "1") (pinfunction "1_1") (pintype "passive"))
    )
    (net (code "21") (name "Net-(IC7-IN)") (class "Default")
      (node (ref "C42") (pin "2") (pinfunction "2_2") (pintype "passive"))
      (node (ref "IC7") (pin "2") (pinfunction "IN_2") (pintype "input"))
      (node (ref "L14") (pin "2") (pinfunction "2_2") (pintype "passive"))
    )
    (net (code "22") (name "Net-(IC7-OUT)") (class "Default")
      (node (ref "C41") (pin "2") (pinfunction "2_2") (pintype "passive"))
      (node (ref "IC7") (pin "6") (pinfunction "OUT_6") (pintype "power_in"))
      (node (ref "L15") (pin "1") (pinfunction "1_1") (pintype "passive"))
    )
    (net (code "23") (name "Net-(L9-Pad1)") (class "Default")
      (node (ref "L9") (pin "1") (pinfunction "1_1") (pintype "passive"))
      (node (ref "R2") (pin "1") (pinfunction "1_1") (pintype "passive"))
      (node (ref "R3") (pin "2") (pinfunction "2_2") (pintype "passive"))
    )
    (net (code "24") (name "Net-(LD1-C)") (class "Default")
      (node (ref "LD1") (pin "1") (pinfunction "C_1") (pintype "passive"))
      (node (ref "R1") (pin "2") (pinfunction "2_2") (pintype "passive"))
    )
    (net (code "25") (name "Net-(U1-IN)") (class "Default")
      (node (ref "C2") (pin "2") (pinfunction "2_2") (pintype "passive"))
      (node (ref "L1") (pin "2") (pinfunction "2_2") (pintype "passive"))
      (node (ref "U1") (pin "1") (pinfunction "IN_1") (pintype "input"))
    )
    (net (code "26") (name "Net-(U1-OUT)") (class "Default")
      (node (ref "C1") (pin "2") (pinfunction "2_2") (pintype "passive"))
      (node (ref "C3") (pin "1") (pinfunction "1_1") (pintype "passive"))
      (node (ref "L2") (pin "1") (pinfunction "1_1") (pintype "passive"))
      (node (ref "U1") (pin "3") (pinfunction "OUT_3") (pintype "output"))
    )
    (net (code "27") (name "Net-(U2-IN)") (class "Default")
      (node (ref "C7") (pin "2") (pinfunction "2_2") (pintype "passive"))
      (node (ref "L3") (pin "2") (pinfunction "2_2") (pintype "passive"))
      (node (ref "U2") (pin "1") (pinfunction "IN_1") (pintype "input"))
    )
    (net (code "28") (name "Net-(U2-OUT)") (class "Default")
      (node (ref "C4") (pin "2") (pinfunction "2_2") (pintype "passive"))
      (node (ref "C8") (pin "1") (pinfunction "1_1") (pintype "passive"))
      (node (ref "L4") (pin "1") (pinfunction "1_1") (pintype "passive"))
      (node (ref "U2") (pin "3") (pinfunction "OUT_3") (pintype "output"))
    )
    (net (code "29") (name "Net-(U3-IN)") (class "Default")
      (node (ref "C10") (pin "2") (pinfunction "2_2") (pintype "passive"))
      (node (ref "L5") (pin "2") (pinfunction "2_2") (pintype "passive"))
      (node (ref "U3") (pin "1") (pinfunction "IN_1") (pintype "input"))
    )
    (net (code "30") (name "Net-(U3-OUT)") (class "Default")
      (node (ref "C11") (pin "1") (pinfunction "1_1") (pintype "passive"))
      (node (ref "C9") (pin "2") (pinfunction "2_2") (pintype "passive"))
      (node (ref "L6") (pin "1") (pinfunction "1_1") (pintype "passive"))
      (node (ref "U3") (pin "3") (pinfunction "OUT_3") (pintype "output"))
    )
    (net (code "31") (name "Net-(U4-IN)") (class "Default")
      (node (ref "C15") (pin "2") (pinfunction "2_2") (pintype "passive"))
      (node (ref "L7") (pin "2") (pinfunction "2_2") (pintype "passive"))
      (node (ref "U4") (pin "1") (pinfunction "IN_1") (pintype "input"))
    )
    (net (code "32") (name "Net-(U4-OUT)") (class "Default")
      (node (ref "C14") (pin "2") (pinfunction "2_2") (pintype "passive"))
      (node (ref "C16") (pin "1") (pinfunction "1_1") (pintype "passive"))
      (node (ref "L8") (pin "1") (pinfunction "1_1") (pintype "passive"))
      (node (ref "U4") (pin "3") (pinfunction "OUT_3") (pintype "output"))
    )
    (net (code "33") (name "Net-(U5-IN+)") (class "Default")
      (node (ref "C23") (pin "2") (pinfunction "2_2") (pintype "passive"))
      (node (ref "R4") (pin "1") (pinfunction "1_1") (pintype "passive"))
      (node (ref "R5") (pin "2") (pinfunction "2_2") (pintype "passive"))
      (node (ref "TP7") (pin "1") (pinfunction "1_1") (pintype "bidirectional"))
      (node (ref "U5") (pin "3") (pinfunction "IN+_3") (pintype "passive"))
      (node (ref "U6") (pin "3") (pinfunction "IN+_3") (pintype "passive"))
      (node (ref "U7") (pin "3") (pinfunction "IN+_3") (pintype "passive"))
      (node (ref "U8") (pin "3") (pinfunction "IN+_3") (pintype "passive"))
    )
    (net (code "34") (name "unconnected-(IC7-NC-Pad1)") (class "Default")
      (node (ref "IC7") (pin "1") (pinfunction "NC_1") (pintype "passive"))
    )
    (net (code "35") (name "unconnected-(IC7-NC-Pad7)") (class "Default")
      (node (ref "IC7") (pin "7") (pinfunction "NC_7") (pintype "passive"))
    )
    (net (code "36") (name "unconnected-(IC7-NC-Pad8)") (class "Default")
      (node (ref "IC7") (pin "8") (pinfunction "NC_8") (pintype "passive"))
    )
    (net (code "37") (name "unconnected-(IC7-TEMP-Pad3)") (class "Default")
      (node (ref "IC7") (pin "3") (pinfunction "TEMP_3") (pintype "passive"))
    )
    (net (code "38") (name "unconnected-(IC7-TRIM-Pad5)") (class "Default")
      (node (ref "IC7") (pin "5") (pinfunction "TRIM_5") (pintype "passive"))
    )
  )
)
